# bytexplore_devboard.net
KiCad netlist of a schematic drawn in EAGLE
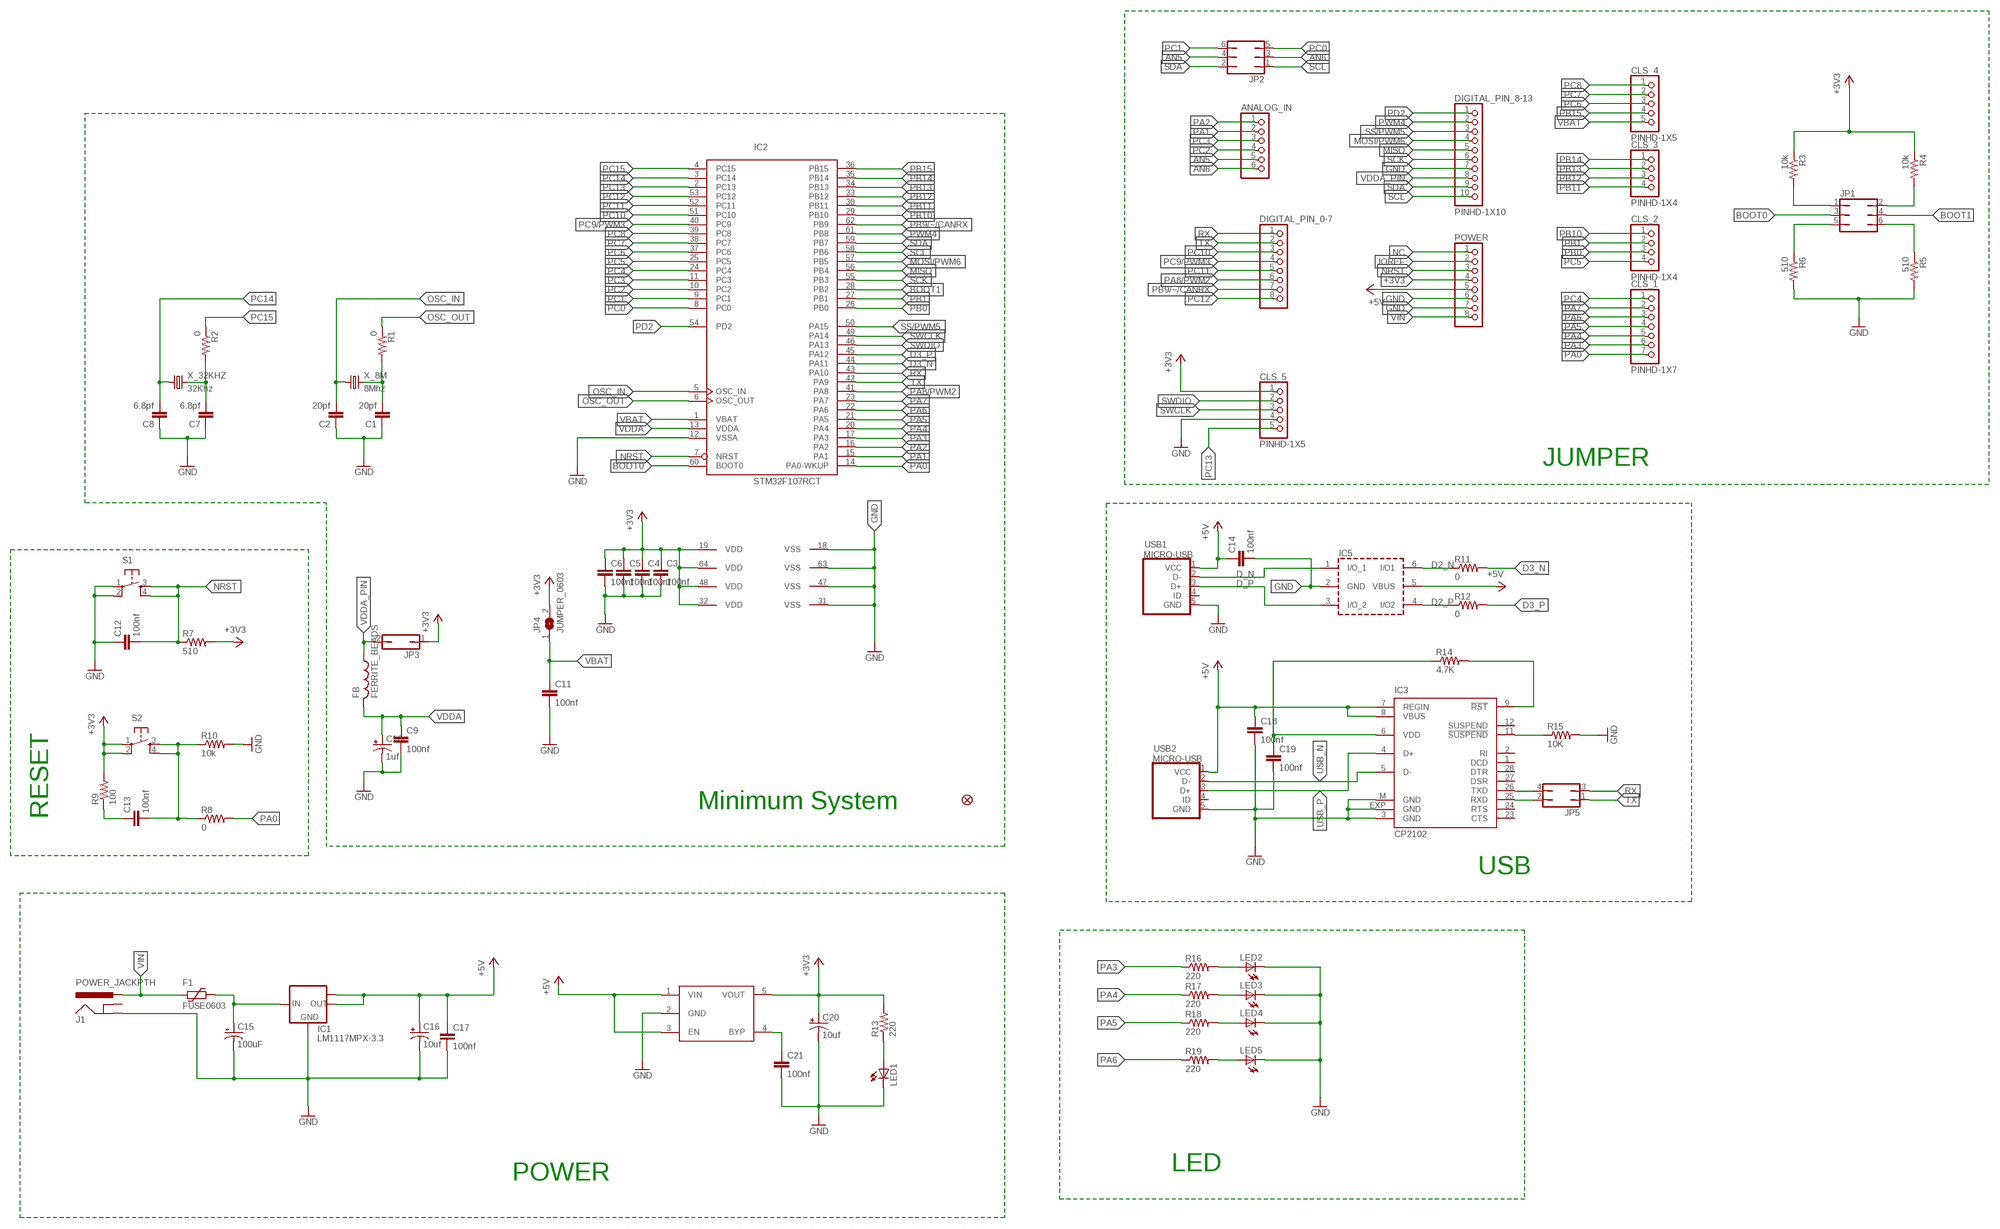
[diagram p0: schematic, sheet 1]

(export (version "E")
  (design (tool "Eeschema 10.0.6"))
  (components
    (comp (ref "ANALOG_IN")
      (value "PINHD-1X6B")
      (footprint "eagle-import:1X06-BIG")
      (libsource (lib "eagle-import") (part "PINHD-1X6B"))
    )
    (comp (ref "C1")
      (value "20pf")
      (footprint "eagle-import:C0603K")
      (libsource (lib "eagle-import") (part "C-EUC0603K"))
    )
    (comp (ref "C2")
      (value "20pf")
      (footprint "eagle-import:C0603K")
      (libsource (lib "eagle-import") (part "C-EUC0603K"))
    )
    (comp (ref "C3")
      (value "100nf")
      (footprint "eagle-import:C0603K")
      (libsource (lib "eagle-import") (part "C-EUC0603K"))
    )
    (comp (ref "C4")
      (value "100nf")
      (footprint "eagle-import:C0603K")
      (libsource (lib "eagle-import") (part "C-EUC0603K"))
    )
    (comp (ref "C5")
      (value "100nf")
      (footprint "eagle-import:C0603K")
      (libsource (lib "eagle-import") (part "C-EUC0603K"))
    )
    (comp (ref "C6")
      (value "100nf")
      (footprint "eagle-import:C0603K")
      (libsource (lib "eagle-import") (part "C-EUC0603K"))
    )
    (comp (ref "C7")
      (value "6.8pf")
      (footprint "eagle-import:C0603K")
      (libsource (lib "eagle-import") (part "C-EUC0603K"))
    )
    (comp (ref "C8")
      (value "6.8pf")
      (footprint "eagle-import:C0603K")
      (libsource (lib "eagle-import") (part "C-EUC0603K"))
    )
    (comp (ref "C9")
      (value "100nf")
      (footprint "eagle-import:C0603K")
      (libsource (lib "eagle-import") (part "C-EUC0603K"))
    )
    (comp (ref "C10")
      (value "1uf")
      (footprint "eagle-import:SMC_B")
      (libsource (lib "eagle-import") (part "CPOL-USSMCB"))
    )
    (comp (ref "C11")
      (value "100nf")
      (footprint "eagle-import:C0603K")
      (libsource (lib "eagle-import") (part "C-EUC0603K"))
    )
    (comp (ref "C12")
      (value "100nf")
      (footprint "eagle-import:C0603K")
      (libsource (lib "eagle-import") (part "C-EUC0603K"))
    )
    (comp (ref "C13")
      (value "100nf")
      (footprint "eagle-import:C0603K")
      (libsource (lib "eagle-import") (part "C-EUC0603K"))
    )
    (comp (ref "C14")
      (value "100nf")
      (footprint "eagle-import:C0603K")
      (libsource (lib "eagle-import") (part "C-EUC0603K"))
    )
    (comp (ref "C15")
      (value "100uF")
      (footprint "eagle-import:PANASONIC_D")
      (libsource (lib "eagle-import") (part "CPOL-USD"))
    )
    (comp (ref "C16")
      (value "10uf")
      (footprint "eagle-import:PANASONIC_B")
      (libsource (lib "eagle-import") (part "CPOL-USB"))
    )
    (comp (ref "C17")
      (value "100nf")
      (footprint "eagle-import:C0603")
      (libsource (lib "eagle-import") (part "C-EUC0603"))
    )
    (comp (ref "C18")
      (value "100nf")
      (footprint "eagle-import:C0603K")
      (libsource (lib "eagle-import") (part "C-EUC0603K"))
    )
    (comp (ref "C19")
      (value "100nf")
      (footprint "eagle-import:C0603K")
      (libsource (lib "eagle-import") (part "C-EUC0603K"))
    )
    (comp (ref "C20")
      (value "10uf")
      (footprint "eagle-import:SMC_A")
      (libsource (lib "eagle-import") (part "CPOL-USSMCA"))
    )
    (comp (ref "C21")
      (value "100nf")
      (footprint "eagle-import:C0603")
      (libsource (lib "eagle-import") (part "C-EUC0603"))
    )
    (comp (ref "CLS_1")
      (value "PINHD-1X7")
      (footprint "eagle-import:1X07-BIG")
      (libsource (lib "eagle-import") (part "PINHD-1X7"))
    )
    (comp (ref "CLS_2")
      (value "PINHD-1X4")
      (footprint "eagle-import:1X04-BIG")
      (libsource (lib "eagle-import") (part "PINHD-1X4"))
    )
    (comp (ref "CLS_3")
      (value "PINHD-1X4")
      (footprint "eagle-import:1X04-BIG")
      (libsource (lib "eagle-import") (part "PINHD-1X4"))
    )
    (comp (ref "CLS_4")
      (value "PINHD-1X5")
      (footprint "eagle-import:1X05-BIG")
      (libsource (lib "eagle-import") (part "PINHD-1X5"))
    )
    (comp (ref "CLS_5")
      (value "PINHD-1X5")
      (footprint "eagle-import:1X05-BIG")
      (libsource (lib "eagle-import") (part "PINHD-1X5"))
    )
    (comp (ref "DIGITAL_PIN_0-7")
      (value "PINHD-1X8BIG")
      (footprint "eagle-import:1X08-BIG")
      (libsource (lib "eagle-import") (part "PINHD-1X8BIG"))
    )
    (comp (ref "DIGITAL_PIN_8-13")
      (value "PINHD-1X10")
      (footprint "eagle-import:1X10-BIG")
      (libsource (lib "eagle-import") (part "PINHD-1X10"))
    )
    (comp (ref "F1")
      (value "FUSE0603")
      (footprint "eagle-import:R0603")
      (libsource (lib "eagle-import") (part "FUSE0603"))
    )
    (comp (ref "FB")
      (value "FERRITE_BEADS")
      (footprint "eagle-import:R0603")
      (libsource (lib "eagle-import") (part "FERRITE_BEADS"))
    )
    (comp (ref "IC1")
      (value "LM1117MPX-3.3")
      (footprint "eagle-import:SOT223")
      (libsource (lib "eagle-import") (part "LM1117MPX-3.3"))
    )
    (comp (ref "IC2")
      (value "STM32F107RCT")
      (footprint "eagle-import:LQFP64")
      (libsource (lib "eagle-import") (part "STM32F107RTC"))
    )
    (comp (ref "IC3")
      (value "CP2102")
      (footprint "eagle-import:MLP28")
      (fields (field (name "MF") "FARNELL") (field (name "MPN") "CP2102-GM"))
      (libsource (lib "eagle-import") (part "CP2102"))
    )
    (comp (ref "IC4")
      (value "MIC5219")
      (footprint "eagle-import:SOT-23-5")
      (libsource (lib "eagle-import") (part "MIC5219"))
    )
    (comp (ref "IC5")
      (value "USBLC6-2SC6")
      (footprint "eagle-import:SOT-23-6L")
      (libsource (lib "eagle-import") (part "USBLC6-2SC6"))
    )
    (comp (ref "J1")
      (value "POWER_JACKPTH")
      (footprint "eagle-import:POWER_JACK_PTH")
      (libsource (lib "eagle-import") (part "POWER_JACKPTH"))
    )
    (comp (ref "JP1")
      (value "JP3Q")
      (footprint "eagle-import:JP3Q")
      (libsource (lib "eagle-import") (part "JP3Q"))
    )
    (comp (ref "JP2")
      (value "JP3Q")
      (footprint "eagle-import:JP3Q")
      (libsource (lib "eagle-import") (part "JP3Q"))
    )
    (comp (ref "JP3")
      (value "JP1Q")
      (footprint "eagle-import:JP1")
      (libsource (lib "eagle-import") (part "JP1Q"))
    )
    (comp (ref "JP4")
      (value "JUMPER_0603")
      (footprint "eagle-import:R0603")
      (libsource (lib "eagle-import") (part "JUMPER_0603"))
    )
    (comp (ref "JP5")
      (value "JP2Q")
      (footprint "eagle-import:JP2Q")
      (libsource (lib "eagle-import") (part "JP2Q"))
    )
    (comp (ref "JP6")
      (value "FIDUCIAL1X2")
      (footprint "eagle-import:FIDUCIAL-1X2")
      (libsource (lib "eagle-import") (part "FIDUCIAL1X2"))
    )
    (comp (ref "LED1")
      (value "LEDSML0603")
      (footprint "eagle-import:SML0603")
      (libsource (lib "eagle-import") (part "LEDSML0603"))
    )
    (comp (ref "LED2")
      (value "LEDSML0603")
      (footprint "eagle-import:SML0603")
      (libsource (lib "eagle-import") (part "LEDSML0603"))
    )
    (comp (ref "LED3")
      (value "LEDSML0603")
      (footprint "eagle-import:SML0603")
      (libsource (lib "eagle-import") (part "LEDSML0603"))
    )
    (comp (ref "LED4")
      (value "LEDSML0603")
      (footprint "eagle-import:SML0603")
      (libsource (lib "eagle-import") (part "LEDSML0603"))
    )
    (comp (ref "LED5")
      (value "LEDSML0603")
      (footprint "eagle-import:SML0603")
      (libsource (lib "eagle-import") (part "LEDSML0603"))
    )
    (comp (ref "POWER")
      (value "PINHD-1X8BIG")
      (footprint "eagle-import:1X08-BIG")
      (libsource (lib "eagle-import") (part "PINHD-1X8BIG"))
    )
    (comp (ref "R1")
      (value "0")
      (footprint "eagle-import:R0603")
      (libsource (lib "eagle-import") (part "R-US_R0603"))
    )
    (comp (ref "R2")
      (value "0")
      (footprint "eagle-import:R0603")
      (libsource (lib "eagle-import") (part "R-US_R0603"))
    )
    (comp (ref "R3")
      (value "10k")
      (footprint "eagle-import:R0603")
      (libsource (lib "eagle-import") (part "R-US_R0603"))
    )
    (comp (ref "R4")
      (value "10k")
      (footprint "eagle-import:R0603")
      (libsource (lib "eagle-import") (part "R-US_R0603"))
    )
    (comp (ref "R5")
      (value "510")
      (footprint "eagle-import:R0603")
      (libsource (lib "eagle-import") (part "R-US_R0603"))
    )
    (comp (ref "R6")
      (value "510")
      (footprint "eagle-import:R0603")
      (libsource (lib "eagle-import") (part "R-US_R0603"))
    )
    (comp (ref "R7")
      (value "510")
      (footprint "eagle-import:R0603")
      (libsource (lib "eagle-import") (part "R-US_R0603"))
    )
    (comp (ref "R8")
      (value "0")
      (footprint "eagle-import:R0603")
      (libsource (lib "eagle-import") (part "R-US_R0603"))
    )
    (comp (ref "R9")
      (value "100")
      (footprint "eagle-import:R0603")
      (libsource (lib "eagle-import") (part "R-US_R0603"))
    )
    (comp (ref "R10")
      (value "10k")
      (footprint "eagle-import:R0603")
      (libsource (lib "eagle-import") (part "R-US_R0603"))
    )
    (comp (ref "R11")
      (value "0")
      (footprint "eagle-import:R0603")
      (libsource (lib "eagle-import") (part "R-US_R0603"))
    )
    (comp (ref "R12")
      (value "0")
      (footprint "eagle-import:R0603")
      (libsource (lib "eagle-import") (part "R-US_R0603"))
    )
    (comp (ref "R13")
      (value "220")
      (footprint "eagle-import:R0603")
      (libsource (lib "eagle-import") (part "R-US_R0603"))
    )
    (comp (ref "R14")
      (value "4.7K")
      (footprint "eagle-import:R0603")
      (libsource (lib "eagle-import") (part "R-US_R0603"))
    )
    (comp (ref "R15")
      (value "10K")
      (footprint "eagle-import:R0603")
      (libsource (lib "eagle-import") (part "R-US_R0603"))
    )
    (comp (ref "R16")
      (value "220")
      (footprint "eagle-import:R0603")
      (libsource (lib "eagle-import") (part "R-US_R0603"))
    )
    (comp (ref "R17")
      (value "220")
      (footprint "eagle-import:R0603")
      (libsource (lib "eagle-import") (part "R-US_R0603"))
    )
    (comp (ref "R18")
      (value "220")
      (footprint "eagle-import:R0603")
      (libsource (lib "eagle-import") (part "R-US_R0603"))
    )
    (comp (ref "R19")
      (value "220")
      (footprint "eagle-import:R0603")
      (libsource (lib "eagle-import") (part "R-US_R0603"))
    )
    (comp (ref "S1")
      (value "TAC_SWITCHPTH")
      (footprint "eagle-import:TACTILE-PTH")
      (libsource (lib "eagle-import") (part "TAC_SWITCHPTH"))
    )
    (comp (ref "S2")
      (value "TAC_SWITCHPTH")
      (footprint "eagle-import:TACTILE-PTH")
      (libsource (lib "eagle-import") (part "TAC_SWITCHPTH"))
    )
    (comp (ref "USB1")
      (value "MICRO-USB")
      (footprint "eagle-import:MICRO-USB")
      (libsource (lib "eagle-import") (part "MICRO-USB"))
    )
    (comp (ref "USB2")
      (value "MICRO-USB")
      (footprint "eagle-import:MICRO-USB")
      (libsource (lib "eagle-import") (part "MICRO-USB"))
    )
    (comp (ref "X_8M")
      (value "8Mhz")
      (footprint "eagle-import:HC49U70")
      (libsource (lib "eagle-import") (part "CRYSTALHC49U70"))
    )
    (comp (ref "X_32KHZ")
      (value "32Khz")
      (footprint "eagle-import:TC26H")
      (libsource (lib "eagle-import") (part "CRYSTALTC26H"))
    )
  )
  (nets
    (net (code "1") (name "+3V3") (class "Default")
      (node (ref "C20") (pin "+") (pinfunction "+_+") (pintype "passive"))
      (node (ref "C3") (pin "1") (pinfunction "1_1") (pintype "passive"))
      (node (ref "C4") (pin "1") (pinfunction "1_1") (pintype "passive"))
      (node (ref "C5") (pin "1") (pinfunction "1_1") (pintype "passive"))
      (node (ref "C6") (pin "1") (pinfunction "1_1") (pintype "passive"))
      (node (ref "CLS_5") (pin "1") (pinfunction "1_1") (pintype "passive"))
      (node (ref "IC2") (pin "19") (pinfunction "VDD_19") (pintype "power_in"))
      (node (ref "IC2") (pin "32") (pinfunction "VDD_32") (pintype "power_in"))
      (node (ref "IC2") (pin "48") (pinfunction "VDD_48") (pintype "power_in"))
      (node (ref "IC2") (pin "64") (pinfunction "VDD_64") (pintype "power_in"))
      (node (ref "IC4") (pin "5") (pinfunction "VOUT_5") (pintype "bidirectional"))
      (node (ref "JP3") (pin "1") (pinfunction "1_1") (pintype "passive"))
      (node (ref "JP4") (pin "2") (pinfunction "2_2") (pintype "passive"))
      (node (ref "POWER") (pin "4") (pinfunction "4_4") (pintype "passive"))
      (node (ref "R13") (pin "2") (pinfunction "2_2") (pintype "passive"))
      (node (ref "R3") (pin "1") (pinfunction "1_1") (pintype "passive"))
      (node (ref "R4") (pin "1") (pinfunction "1_1") (pintype "passive"))
      (node (ref "R7") (pin "2") (pinfunction "2_2") (pintype "passive"))
      (node (ref "R9") (pin "2") (pinfunction "2_2") (pintype "passive"))
      (node (ref "S2") (pin "1") (pinfunction "1_1") (pintype "passive"))
      (node (ref "S2") (pin "2") (pinfunction "2_2") (pintype "passive"))
    )
    (net (code "2") (name "+5V") (class "Default")
      (node (ref "C14") (pin "1") (pinfunction "1_1") (pintype "passive"))
      (node (ref "C16") (pin "+") (pinfunction "+_+") (pintype "passive"))
      (node (ref "C17") (pin "1") (pinfunction "1_1") (pintype "passive"))
      (node (ref "C18") (pin "1") (pinfunction "1_1") (pintype "passive"))
      (node (ref "IC1") (pin "2") (pinfunction "OUT_2") (pintype "passive"))
      (node (ref "IC1") (pin "TAB") (pinfunction "OUT1_TAB") (pintype "passive"))
      (node (ref "IC3") (pin "7") (pinfunction "REGIN_7") (pintype "passive"))
      (node (ref "IC3") (pin "8") (pinfunction "VBUS_8") (pintype "input"))
      (node (ref "IC4") (pin "1") (pinfunction "VIN_1") (pintype "bidirectional"))
      (node (ref "IC4") (pin "3") (pinfunction "EN_3") (pintype "bidirectional"))
      (node (ref "IC5") (pin "5") (pinfunction "VBUS_5") (pintype "bidirectional"))
      (node (ref "POWER") (pin "5") (pinfunction "5_5") (pintype "passive"))
      (node (ref "USB1") (pin "1") (pinfunction "VCC_1") (pintype "power_in"))
      (node (ref "USB2") (pin "1") (pinfunction "VCC_1") (pintype "power_in"))
    )
    (net (code "3") (name "/D2_N") (class "Default")
      (node (ref "IC5") (pin "6") (pinfunction "I/O1_6") (pintype "bidirectional"))
      (node (ref "R11") (pin "1") (pinfunction "1_1") (pintype "passive"))
    )
    (net (code "4") (name "/D2_P") (class "Default")
      (node (ref "IC5") (pin "4") (pinfunction "I/O2_4") (pintype "bidirectional"))
      (node (ref "R12") (pin "1") (pinfunction "1_1") (pintype "passive"))
    )
    (net (code "5") (name "/D_N") (class "Default")
      (node (ref "IC5") (pin "1") (pinfunction "I/O_1_1") (pintype "bidirectional"))
      (node (ref "USB1") (pin "2") (pinfunction "D-_2") (pintype "bidirectional"))
    )
    (net (code "6") (name "/D_P") (class "Default")
      (node (ref "IC5") (pin "3") (pinfunction "I/O_2_3") (pintype "bidirectional"))
      (node (ref "USB1") (pin "3") (pinfunction "D+_3") (pintype "bidirectional"))
    )
    (net (code "7") (name "/PB9{slash}~{{slash}CANRX}") (class "Default")
      (node (ref "DIGITAL_PIN_0-7") (pin "7") (pinfunction "7_7") (pintype "passive"))
      (node (ref "IC2") (pin "62") (pinfunction "PB9_62") (pintype "bidirectional"))
    )
    (net (code "8") (name "AN5") (class "Default")
      (node (ref "ANALOG_IN") (pin "5") (pinfunction "5_5") (pintype "passive"))
      (node (ref "JP2") (pin "4") (pinfunction "4_4") (pintype "passive"))
    )
    (net (code "9") (name "AN6") (class "Default")
      (node (ref "ANALOG_IN") (pin "6") (pinfunction "6_6") (pintype "passive"))
      (node (ref "JP2") (pin "3") (pinfunction "3_3") (pintype "passive"))
    )
    (net (code "10") (name "BOOT0") (class "Default")
      (node (ref "IC2") (pin "60") (pinfunction "BOOT0_60") (pintype "input"))
      (node (ref "JP1") (pin "3") (pinfunction "3_3") (pintype "passive"))
    )
    (net (code "11") (name "BOOT1") (class "Default")
      (node (ref "IC2") (pin "28") (pinfunction "PB2_28") (pintype "bidirectional"))
      (node (ref "JP1") (pin "4") (pinfunction "4_4") (pintype "passive"))
    )
    (net (code "12") (name "D3_N") (class "Default")
      (node (ref "IC2") (pin "44") (pinfunction "PA11_44") (pintype "bidirectional"))
      (node (ref "R11") (pin "2") (pinfunction "2_2") (pintype "passive"))
    )
    (net (code "13") (name "D3_P") (class "Default")
      (node (ref "IC2") (pin "45") (pinfunction "PA12_45") (pintype "bidirectional"))
      (node (ref "R12") (pin "2") (pinfunction "2_2") (pintype "passive"))
    )
    (net (code "14") (name "GND") (class "Default")
      (node (ref "C1") (pin "1") (pinfunction "1_1") (pintype "passive"))
      (node (ref "C10") (pin "-") (pinfunction "-_-") (pintype "passive"))
      (node (ref "C11") (pin "2") (pinfunction "2_2") (pintype "passive"))
      (node (ref "C12") (pin "1") (pinfunction "1_1") (pintype "passive"))
      (node (ref "C14") (pin "2") (pinfunction "2_2") (pintype "passive"))
      (node (ref "C15") (pin "-") (pinfunction "-_-") (pintype "passive"))
      (node (ref "C16") (pin "-") (pinfunction "-_-") (pintype "passive"))
      (node (ref "C17") (pin "2") (pinfunction "2_2") (pintype "passive"))
      (node (ref "C18") (pin "2") (pinfunction "2_2") (pintype "passive"))
      (node (ref "C19") (pin "2") (pinfunction "2_2") (pintype "passive"))
      (node (ref "C2") (pin "1") (pinfunction "1_1") (pintype "passive"))
      (node (ref "C20") (pin "-") (pinfunction "-_-") (pintype "passive"))
      (node (ref "C21") (pin "2") (pinfunction "2_2") (pintype "passive"))
      (node (ref "C3") (pin "2") (pinfunction "2_2") (pintype "passive"))
      (node (ref "C4") (pin "2") (pinfunction "2_2") (pintype "passive"))
      (node (ref "C5") (pin "2") (pinfunction "2_2") (pintype "passive"))
      (node (ref "C6") (pin "2") (pinfunction "2_2") (pintype "passive"))
      (node (ref "C7") (pin "1") (pinfunction "1_1") (pintype "passive"))
      (node (ref "C8") (pin "1") (pinfunction "1_1") (pintype "passive"))
      (node (ref "C9") (pin "2") (pinfunction "2_2") (pintype "passive"))
      (node (ref "CLS_5") (pin "4") (pinfunction "4_4") (pintype "passive"))
      (node (ref "DIGITAL_PIN_8-13") (pin "7") (pinfunction "7_7") (pintype "passive"))
      (node (ref "IC1") (pin "1") (pinfunction "GND_1") (pintype "input"))
      (node (ref "IC2") (pin "12") (pinfunction "VSSA_12") (pintype "power_in"))
      (node (ref "IC2") (pin "18") (pinfunction "VSS_18") (pintype "power_in"))
      (node (ref "IC2") (pin "31") (pinfunction "VSS_31") (pintype "power_in"))
      (node (ref "IC2") (pin "47") (pinfunction "VSS_47") (pintype "power_in"))
      (node (ref "IC2") (pin "63") (pinfunction "VSS_63") (pintype "power_in"))
      (node (ref "IC3") (pin "3") (pinfunction "GND_3") (pintype "power_in"))
      (node (ref "IC3") (pin "EXP") (pinfunction "GND_EXP") (pintype "power_in"))
      (node (ref "IC3") (pin "M") (pinfunction "GND_M") (pintype "power_in"))
      (node (ref "IC4") (pin "2") (pinfunction "GND_2") (pintype "bidirectional"))
      (node (ref "IC5") (pin "2") (pinfunction "GND_2") (pintype "bidirectional"))
      (node (ref "J1") (pin "GND") (pinfunction "GND_GND") (pintype "bidirectional"))
      (node (ref "LED1") (pin "C") (pinfunction "C_C") (pintype "passive"))
      (node (ref "LED2") (pin "C") (pinfunction "C_C") (pintype "passive"))
      (node (ref "LED3") (pin "C") (pinfunction "C_C") (pintype "passive"))
      (node (ref "LED4") (pin "C") (pinfunction "C_C") (pintype "passive"))
      (node (ref "LED5") (pin "C") (pinfunction "C_C") (pintype "passive"))
      (node (ref "POWER") (pin "6") (pinfunction "6_6") (pintype "passive"))
      (node (ref "POWER") (pin "7") (pinfunction "7_7") (pintype "passive"))
      (node (ref "R10") (pin "2") (pinfunction "2_2") (pintype "passive"))
      (node (ref "R15") (pin "2") (pinfunction "2_2") (pintype "passive"))
      (node (ref "R5") (pin "2") (pinfunction "2_2") (pintype "passive"))
      (node (ref "R6") (pin "2") (pinfunction "2_2") (pintype "passive"))
      (node (ref "S1") (pin "1") (pinfunction "1_1") (pintype "passive"))
      (node (ref "S1") (pin "2") (pinfunction "2_2") (pintype "passive"))
      (node (ref "USB1") (pin "5") (pinfunction "GND_5") (pintype "power_in"))
      (node (ref "USB2") (pin "5") (pinfunction "GND_5") (pintype "power_in"))
    )
    (net (code "15") (name "IOREF") (class "Default")
      (node (ref "POWER") (pin "2") (pinfunction "2_2") (pintype "passive"))
    )
    (net (code "16") (name "MISO") (class "Default")
      (node (ref "DIGITAL_PIN_8-13") (pin "5") (pinfunction "5_5") (pintype "passive"))
      (node (ref "IC2") (pin "56") (pinfunction "PB4_56") (pintype "bidirectional"))
    )
    (net (code "17") (name "MOSI{slash}PWM6") (class "Default")
      (node (ref "DIGITAL_PIN_8-13") (pin "4") (pinfunction "4_4") (pintype "passive"))
      (node (ref "IC2") (pin "57") (pinfunction "PB5_57") (pintype "bidirectional"))
    )
    (net (code "18") (name "NC") (class "Default")
      (node (ref "POWER") (pin "1") (pinfunction "1_1") (pintype "passive"))
    )
    (net (code "19") (name "NRST") (class "Default")
      (node (ref "C12") (pin "2") (pinfunction "2_2") (pintype "passive"))
      (node (ref "IC2") (pin "7") (pinfunction "NRST_7") (pintype "bidirectional"))
      (node (ref "POWER") (pin "3") (pinfunction "3_3") (pintype "passive"))
      (node (ref "R7") (pin "1") (pinfunction "1_1") (pintype "passive"))
      (node (ref "S1") (pin "3") (pinfunction "3_3") (pintype "passive"))
      (node (ref "S1") (pin "4") (pinfunction "4_4") (pintype "passive"))
    )
    (net (code "20") (name "Net-(C1-Pad2)") (class "Default")
      (node (ref "C1") (pin "2") (pinfunction "2_2") (pintype "passive"))
      (node (ref "R1") (pin "2") (pinfunction "2_2") (pintype "passive"))
      (node (ref "X_8M") (pin "2") (pinfunction "2_2") (pintype "passive"))
    )
    (net (code "21") (name "Net-(C7-Pad2)") (class "Default")
      (node (ref "C7") (pin "2") (pinfunction "2_2") (pintype "passive"))
      (node (ref "R2") (pin "2") (pinfunction "2_2") (pintype "passive"))
      (node (ref "X_32KHZ") (pin "2") (pinfunction "2_2") (pintype "passive"))
    )
    (net (code "22") (name "Net-(C13-Pad1)") (class "Default")
      (node (ref "C13") (pin "1") (pinfunction "1_1") (pintype "passive"))
      (node (ref "R9") (pin "1") (pinfunction "1_1") (pintype "passive"))
    )
    (net (code "23") (name "Net-(C13-Pad2)") (class "Default")
      (node (ref "C13") (pin "2") (pinfunction "2_2") (pintype "passive"))
      (node (ref "R10") (pin "1") (pinfunction "1_1") (pintype "passive"))
      (node (ref "R8") (pin "1") (pinfunction "1_1") (pintype "passive"))
      (node (ref "S2") (pin "3") (pinfunction "3_3") (pintype "passive"))
      (node (ref "S2") (pin "4") (pinfunction "4_4") (pintype "passive"))
    )
    (net (code "24") (name "Net-(IC1-IN)") (class "Default")
      (node (ref "C15") (pin "+") (pinfunction "+_+") (pintype "passive"))
      (node (ref "F1") (pin "1") (pinfunction "1_1") (pintype "passive"))
      (node (ref "IC1") (pin "3") (pinfunction "IN_3") (pintype "input"))
    )
    (net (code "25") (name "Net-(IC3-RXD)") (class "Default")
      (node (ref "IC3") (pin "25") (pinfunction "RXD_25") (pintype "input"))
      (node (ref "JP5") (pin "2") (pinfunction "2_2") (pintype "passive"))
    )
    (net (code "26") (name "Net-(IC3-TXD)") (class "Default")
      (node (ref "IC3") (pin "26") (pinfunction "TXD_26") (pintype "output"))
      (node (ref "JP5") (pin "4") (pinfunction "4_4") (pintype "passive"))
    )
    (net (code "27") (name "Net-(IC3-VDD)") (class "Default")
      (node (ref "C19") (pin "1") (pinfunction "1_1") (pintype "passive"))
      (node (ref "IC3") (pin "6") (pinfunction "VDD_6") (pintype "power_in"))
      (node (ref "R14") (pin "1") (pinfunction "1_1") (pintype "passive"))
    )
    (net (code "28") (name "Net-(IC3-~{RST})") (class "Default")
      (node (ref "IC3") (pin "9") (pinfunction "~{RST}_9") (pintype "bidirectional"))
      (node (ref "R14") (pin "2") (pinfunction "2_2") (pintype "passive"))
    )
    (net (code "29") (name "Net-(IC3-~{SUSPEND})") (class "Default")
      (node (ref "IC3") (pin "11") (pinfunction "~{SUSPEND}_11") (pintype "output"))
      (node (ref "R15") (pin "1") (pinfunction "1_1") (pintype "passive"))
    )
    (net (code "30") (name "Net-(IC4-BYP)") (class "Default")
      (node (ref "C21") (pin "1") (pinfunction "1_1") (pintype "passive"))
      (node (ref "IC4") (pin "4") (pinfunction "BYP_4") (pintype "bidirectional"))
    )
    (net (code "31") (name "Net-(JP1-Pad1)") (class "Default")
      (node (ref "JP1") (pin "1") (pinfunction "1_1") (pintype "passive"))
      (node (ref "R3") (pin "2") (pinfunction "2_2") (pintype "passive"))
    )
    (net (code "32") (name "Net-(JP1-Pad2)") (class "Default")
      (node (ref "JP1") (pin "2") (pinfunction "2_2") (pintype "passive"))
      (node (ref "R4") (pin "2") (pinfunction "2_2") (pintype "passive"))
    )
    (net (code "33") (name "Net-(JP1-Pad5)") (class "Default")
      (node (ref "JP1") (pin "5") (pinfunction "5_5") (pintype "passive"))
      (node (ref "R6") (pin "1") (pinfunction "1_1") (pintype "passive"))
    )
    (net (code "34") (name "Net-(JP1-Pad6)") (class "Default")
      (node (ref "JP1") (pin "6") (pinfunction "6_6") (pintype "passive"))
      (node (ref "R5") (pin "1") (pinfunction "1_1") (pintype "passive"))
    )
    (net (code "35") (name "Net-(LED1-PadA)") (class "Default")
      (node (ref "LED1") (pin "A") (pinfunction "A_A") (pintype "passive"))
      (node (ref "R13") (pin "1") (pinfunction "1_1") (pintype "passive"))
    )
    (net (code "36") (name "Net-(LED2-PadA)") (class "Default")
      (node (ref "LED2") (pin "A") (pinfunction "A_A") (pintype "passive"))
      (node (ref "R16") (pin "2") (pinfunction "2_2") (pintype "passive"))
    )
    (net (code "37") (name "Net-(LED3-PadA)") (class "Default")
      (node (ref "LED3") (pin "A") (pinfunction "A_A") (pintype "passive"))
      (node (ref "R17") (pin "2") (pinfunction "2_2") (pintype "passive"))
    )
    (net (code "38") (name "Net-(LED4-PadA)") (class "Default")
      (node (ref "LED4") (pin "A") (pinfunction "A_A") (pintype "passive"))
      (node (ref "R18") (pin "2") (pinfunction "2_2") (pintype "passive"))
    )
    (net (code "39") (name "Net-(LED5-PadA)") (class "Default")
      (node (ref "LED5") (pin "A") (pinfunction "A_A") (pintype "passive"))
      (node (ref "R19") (pin "2") (pinfunction "2_2") (pintype "passive"))
    )
    (net (code "40") (name "OSC_IN") (class "Default")
      (node (ref "C2") (pin "2") (pinfunction "2_2") (pintype "passive"))
      (node (ref "IC2") (pin "5") (pinfunction "OSC_IN_5") (pintype "bidirectional"))
      (node (ref "X_8M") (pin "1") (pinfunction "1_1") (pintype "passive"))
    )
    (net (code "41") (name "OSC_OUT") (class "Default")
      (node (ref "IC2") (pin "6") (pinfunction "OSC_OUT_6") (pintype "bidirectional"))
      (node (ref "R1") (pin "1") (pinfunction "1_1") (pintype "passive"))
    )
    (net (code "42") (name "PA0") (class "Default")
      (node (ref "CLS_1") (pin "7") (pinfunction "7_7") (pintype "passive"))
      (node (ref "IC2") (pin "14") (pinfunction "PA0-WKUP_14") (pintype "bidirectional"))
      (node (ref "R8") (pin "2") (pinfunction "2_2") (pintype "passive"))
    )
    (net (code "43") (name "PA1") (class "Default")
      (node (ref "ANALOG_IN") (pin "2") (pinfunction "2_2") (pintype "passive"))
      (node (ref "IC2") (pin "15") (pinfunction "PA1_15") (pintype "bidirectional"))
    )
    (net (code "44") (name "PA2") (class "Default")
      (node (ref "ANALOG_IN") (pin "1") (pinfunction "1_1") (pintype "passive"))
      (node (ref "IC2") (pin "16") (pinfunction "PA2_16") (pintype "bidirectional"))
    )
    (net (code "45") (name "PA3") (class "Default")
      (node (ref "CLS_1") (pin "6") (pinfunction "6_6") (pintype "passive"))
      (node (ref "IC2") (pin "17") (pinfunction "PA3_17") (pintype "bidirectional"))
      (node (ref "R16") (pin "1") (pinfunction "1_1") (pintype "passive"))
    )
    (net (code "46") (name "PA4") (class "Default")
      (node (ref "CLS_1") (pin "5") (pinfunction "5_5") (pintype "passive"))
      (node (ref "IC2") (pin "20") (pinfunction "PA4_20") (pintype "bidirectional"))
      (node (ref "R17") (pin "1") (pinfunction "1_1") (pintype "passive"))
    )
    (net (code "47") (name "PA5") (class "Default")
      (node (ref "CLS_1") (pin "4") (pinfunction "4_4") (pintype "passive"))
      (node (ref "IC2") (pin "21") (pinfunction "PA5_21") (pintype "bidirectional"))
      (node (ref "R18") (pin "1") (pinfunction "1_1") (pintype "passive"))
    )
    (net (code "48") (name "PA6") (class "Default")
      (node (ref "CLS_1") (pin "3") (pinfunction "3_3") (pintype "passive"))
      (node (ref "IC2") (pin "22") (pinfunction "PA6_22") (pintype "bidirectional"))
      (node (ref "R19") (pin "1") (pinfunction "1_1") (pintype "passive"))
    )
    (net (code "49") (name "PA7") (class "Default")
      (node (ref "CLS_1") (pin "2") (pinfunction "2_2") (pintype "passive"))
      (node (ref "IC2") (pin "23") (pinfunction "PA7_23") (pintype "bidirectional"))
    )
    (net (code "50") (name "PA8{slash}PWM2") (class "Default")
      (node (ref "DIGITAL_PIN_0-7") (pin "6") (pinfunction "6_6") (pintype "passive"))
      (node (ref "IC2") (pin "41") (pinfunction "PA8_41") (pintype "bidirectional"))
    )
    (net (code "51") (name "PB0") (class "Default")
      (node (ref "CLS_2") (pin "3") (pinfunction "3_3") (pintype "passive"))
      (node (ref "IC2") (pin "26") (pinfunction "PB0_26") (pintype "bidirectional"))
    )
    (net (code "52") (name "PB1") (class "Default")
      (node (ref "CLS_2") (pin "2") (pinfunction "2_2") (pintype "passive"))
      (node (ref "IC2") (pin "27") (pinfunction "PB1_27") (pintype "bidirectional"))
    )
    (net (code "53") (name "PB10") (class "Default")
      (node (ref "CLS_2") (pin "1") (pinfunction "1_1") (pintype "passive"))
      (node (ref "IC2") (pin "29") (pinfunction "PB10_29") (pintype "bidirectional"))
    )
    (net (code "54") (name "PB11") (class "Default")
      (node (ref "CLS_3") (pin "4") (pinfunction "4_4") (pintype "passive"))
      (node (ref "IC2") (pin "30") (pinfunction "PB11_30") (pintype "bidirectional"))
    )
    (net (code "55") (name "PB12") (class "Default")
      (node (ref "CLS_3") (pin "3") (pinfunction "3_3") (pintype "passive"))
      (node (ref "IC2") (pin "33") (pinfunction "PB12_33") (pintype "bidirectional"))
    )
    (net (code "56") (name "PB13") (class "Default")
      (node (ref "CLS_3") (pin "2") (pinfunction "2_2") (pintype "passive"))
      (node (ref "IC2") (pin "34") (pinfunction "PB13_34") (pintype "bidirectional"))
    )
    (net (code "57") (name "PB14") (class "Default")
      (node (ref "CLS_3") (pin "1") (pinfunction "1_1") (pintype "passive"))
      (node (ref "IC2") (pin "35") (pinfunction "PB14_35") (pintype "bidirectional"))
    )
    (net (code "58") (name "PB15") (class "Default")
      (node (ref "CLS_4") (pin "4") (pinfunction "4_4") (pintype "passive"))
      (node (ref "IC2") (pin "36") (pinfunction "PB15_36") (pintype "bidirectional"))
    )
    (net (code "59") (name "PC0") (class "Default")
      (node (ref "IC2") (pin "8") (pinfunction "PC0_8") (pintype "bidirectional"))
      (node (ref "JP2") (pin "5") (pinfunction "5_5") (pintype "passive"))
    )
    (net (code "60") (name "PC1") (class "Default")
      (node (ref "IC2") (pin "9") (pinfunction "PC1_9") (pintype "bidirectional"))
      (node (ref "JP2") (pin "6") (pinfunction "6_6") (pintype "passive"))
    )
    (net (code "61") (name "PC2") (class "Default")
      (node (ref "ANALOG_IN") (pin "4") (pinfunction "4_4") (pintype "passive"))
      (node (ref "IC2") (pin "10") (pinfunction "PC2_10") (pintype "bidirectional"))
    )
    (net (code "62") (name "PC3") (class "Default")
      (node (ref "ANALOG_IN") (pin "3") (pinfunction "3_3") (pintype "passive"))
      (node (ref "IC2") (pin "11") (pinfunction "PC3_11") (pintype "bidirectional"))
    )
    (net (code "63") (name "PC4") (class "Default")
      (node (ref "CLS_1") (pin "1") (pinfunction "1_1") (pintype "passive"))
      (node (ref "IC2") (pin "24") (pinfunction "PC4_24") (pintype "bidirectional"))
    )
    (net (code "64") (name "PC5") (class "Default")
      (node (ref "CLS_2") (pin "4") (pinfunction "4_4") (pintype "passive"))
      (node (ref "IC2") (pin "25") (pinfunction "PC5_25") (pintype "bidirectional"))
    )
    (net (code "65") (name "PC6") (class "Default")
      (node (ref "CLS_4") (pin "3") (pinfunction "3_3") (pintype "passive"))
      (node (ref "IC2") (pin "37") (pinfunction "PC6_37") (pintype "bidirectional"))
    )
    (net (code "66") (name "PC7") (class "Default")
      (node (ref "CLS_4") (pin "2") (pinfunction "2_2") (pintype "passive"))
      (node (ref "IC2") (pin "38") (pinfunction "PC7_38") (pintype "bidirectional"))
    )
    (net (code "67") (name "PC8") (class "Default")
      (node (ref "CLS_4") (pin "1") (pinfunction "1_1") (pintype "passive"))
      (node (ref "IC2") (pin "39") (pinfunction "PC8_39") (pintype "bidirectional"))
    )
    (net (code "68") (name "PC9{slash}PWM3") (class "Default")
      (node (ref "DIGITAL_PIN_0-7") (pin "4") (pinfunction "4_4") (pintype "passive"))
      (node (ref "IC2") (pin "40") (pinfunction "PC9_40") (pintype "bidirectional"))
    )
    (net (code "69") (name "PC10") (class "Default")
      (node (ref "DIGITAL_PIN_0-7") (pin "3") (pinfunction "3_3") (pintype "passive"))
      (node (ref "IC2") (pin "51") (pinfunction "PC10_51") (pintype "bidirectional"))
    )
    (net (code "70") (name "PC11") (class "Default")
      (node (ref "DIGITAL_PIN_0-7") (pin "5") (pinfunction "5_5") (pintype "passive"))
      (node (ref "IC2") (pin "52") (pinfunction "PC11_52") (pintype "bidirectional"))
    )
    (net (code "71") (name "PC12") (class "Default")
      (node (ref "DIGITAL_PIN_0-7") (pin "8") (pinfunction "8_8") (pintype "passive"))
      (node (ref "IC2") (pin "53") (pinfunction "PC12_53") (pintype "bidirectional"))
    )
    (net (code "72") (name "PC13") (class "Default")
      (node (ref "CLS_5") (pin "5") (pinfunction "5_5") (pintype "passive"))
      (node (ref "IC2") (pin "2") (pinfunction "PC13_2") (pintype "bidirectional"))
    )
    (net (code "73") (name "PC14") (class "Default")
      (node (ref "C8") (pin "2") (pinfunction "2_2") (pintype "passive"))
      (node (ref "IC2") (pin "3") (pinfunction "PC14_3") (pintype "bidirectional"))
      (node (ref "X_32KHZ") (pin "1") (pinfunction "1_1") (pintype "passive"))
    )
    (net (code "74") (name "PC15") (class "Default")
      (node (ref "IC2") (pin "4") (pinfunction "PC15_4") (pintype "bidirectional"))
      (node (ref "R2") (pin "1") (pinfunction "1_1") (pintype "passive"))
    )
    (net (code "75") (name "PD2") (class "Default")
      (node (ref "DIGITAL_PIN_8-13") (pin "1") (pinfunction "1_1") (pintype "passive"))
      (node (ref "IC2") (pin "54") (pinfunction "PD2_54") (pintype "bidirectional"))
    )
    (net (code "76") (name "PWM4") (class "Default")
      (node (ref "DIGITAL_PIN_8-13") (pin "2") (pinfunction "2_2") (pintype "passive"))
      (node (ref "IC2") (pin "61") (pinfunction "PB8_61") (pintype "bidirectional"))
    )
    (net (code "77") (name "RX") (class "Default")
      (node (ref "DIGITAL_PIN_0-7") (pin "1") (pinfunction "1_1") (pintype "passive"))
      (node (ref "IC2") (pin "43") (pinfunction "PA10_43") (pintype "bidirectional"))
      (node (ref "JP5") (pin "3") (pinfunction "3_3") (pintype "passive"))
    )
    (net (code "78") (name "SCK") (class "Default")
      (node (ref "DIGITAL_PIN_8-13") (pin "6") (pinfunction "6_6") (pintype "passive"))
      (node (ref "IC2") (pin "55") (pinfunction "PB3_55") (pintype "bidirectional"))
    )
    (net (code "79") (name "SCL") (class "Default")
      (node (ref "DIGITAL_PIN_8-13") (pin "10") (pinfunction "10_10") (pintype "passive"))
      (node (ref "IC2") (pin "58") (pinfunction "PB6_58") (pintype "bidirectional"))
      (node (ref "JP2") (pin "1") (pinfunction "1_1") (pintype "passive"))
    )
    (net (code "80") (name "SDA") (class "Default")
      (node (ref "DIGITAL_PIN_8-13") (pin "9") (pinfunction "9_9") (pintype "passive"))
      (node (ref "IC2") (pin "59") (pinfunction "PB7_59") (pintype "bidirectional"))
      (node (ref "JP2") (pin "2") (pinfunction "2_2") (pintype "passive"))
    )
    (net (code "81") (name "SS{slash}PWM5") (class "Default")
      (node (ref "DIGITAL_PIN_8-13") (pin "3") (pinfunction "3_3") (pintype "passive"))
      (node (ref "IC2") (pin "50") (pinfunction "PA15_50") (pintype "bidirectional"))
    )
    (net (code "82") (name "SWCLK") (class "Default")
      (node (ref "CLS_5") (pin "3") (pinfunction "3_3") (pintype "passive"))
      (node (ref "IC2") (pin "49") (pinfunction "PA14_49") (pintype "bidirectional"))
    )
    (net (code "83") (name "SWDIO") (class "Default")
      (node (ref "CLS_5") (pin "2") (pinfunction "2_2") (pintype "passive"))
      (node (ref "IC2") (pin "46") (pinfunction "PA13_46") (pintype "bidirectional"))
    )
    (net (code "84") (name "TX") (class "Default")
      (node (ref "DIGITAL_PIN_0-7") (pin "2") (pinfunction "2_2") (pintype "passive"))
      (node (ref "IC2") (pin "42") (pinfunction "PA9_42") (pintype "bidirectional"))
      (node (ref "JP5") (pin "1") (pinfunction "1_1") (pintype "passive"))
    )
    (net (code "85") (name "USB_N") (class "Default")
      (node (ref "IC3") (pin "5") (pinfunction "D-_5") (pintype "bidirectional"))
      (node (ref "USB2") (pin "2") (pinfunction "D-_2") (pintype "bidirectional"))
    )
    (net (code "86") (name "USB_P") (class "Default")
      (node (ref "IC3") (pin "4") (pinfunction "D+_4") (pintype "bidirectional"))
      (node (ref "USB2") (pin "3") (pinfunction "D+_3") (pintype "bidirectional"))
    )
    (net (code "87") (name "VBAT") (class "Default")
      (node (ref "C11") (pin "1") (pinfunction "1_1") (pintype "passive"))
      (node (ref "CLS_4") (pin "5") (pinfunction "5_5") (pintype "passive"))
      (node (ref "IC2") (pin "1") (pinfunction "VBAT_1") (pintype "power_in"))
      (node (ref "JP4") (pin "1") (pinfunction "1_1") (pintype "passive"))
    )
    (net (code "88") (name "VDDA") (class "Default")
      (node (ref "C10") (pin "+") (pinfunction "+_+") (pintype "passive"))
      (node (ref "C9") (pin "1") (pinfunction "1_1") (pintype "passive"))
      (node (ref "FB") (pin "2") (pinfunction "2_2") (pintype "passive"))
      (node (ref "IC2") (pin "13") (pinfunction "VDDA_13") (pintype "power_in"))
    )
    (net (code "89") (name "VDDA_PIN") (class "Default")
      (node (ref "DIGITAL_PIN_8-13") (pin "8") (pinfunction "8_8") (pintype "passive"))
      (node (ref "FB") (pin "1") (pinfunction "1_1") (pintype "passive"))
      (node (ref "JP3") (pin "2") (pinfunction "2_2") (pintype "passive"))
    )
    (net (code "90") (name "VIN") (class "Default")
      (node (ref "F1") (pin "2") (pinfunction "2_2") (pintype "passive"))
      (node (ref "J1") (pin "PWR") (pinfunction "PWR_PWR") (pintype "bidirectional"))
      (node (ref "POWER") (pin "8") (pinfunction "8_8") (pintype "passive"))
    )
    (net (code "91") (name "unconnected-(IC3-CTS-Pad23)") (class "Default")
      (node (ref "IC3") (pin "23") (pinfunction "CTS_23") (pintype "input"))
    )
    (net (code "92") (name "unconnected-(IC3-DCD-Pad1)") (class "Default")
      (node (ref "IC3") (pin "1") (pinfunction "DCD_1") (pintype "input"))
    )
    (net (code "93") (name "unconnected-(IC3-DSR-Pad27)") (class "Default")
      (node (ref "IC3") (pin "27") (pinfunction "DSR_27") (pintype "input"))
    )
    (net (code "94") (name "unconnected-(IC3-DTR-Pad28)") (class "Default")
      (node (ref "IC3") (pin "28") (pinfunction "DTR_28") (pintype "output"))
    )
    (net (code "95") (name "unconnected-(IC3-RI-Pad2)") (class "Default")
      (node (ref "IC3") (pin "2") (pinfunction "RI_2") (pintype "input"))
    )
    (net (code "96") (name "unconnected-(IC3-RTS-Pad24)") (class "Default")
      (node (ref "IC3") (pin "24") (pinfunction "RTS_24") (pintype "output"))
    )
    (net (code "97") (name "unconnected-(IC3-SUSPEND-Pad12)") (class "Default")
      (node (ref "IC3") (pin "12") (pinfunction "SUSPEND_12") (pintype "output"))
    )
    (net (code "98") (name "unconnected-(J1-GNDBREAK-PadGNB)") (class "Default")
      (node (ref "J1") (pin "GNB") (pinfunction "GNDBREAK_GNB") (pintype "bidirectional"))
    )
    (net (code "99") (name "unconnected-(USB1-ID-Pad4)") (class "Default")
      (node (ref "USB1") (pin "4") (pinfunction "ID_4") (pintype "bidirectional"))
    )
    (net (code "100") (name "unconnected-(USB2-ID-Pad4)") (class "Default")
      (node (ref "USB2") (pin "4") (pinfunction "ID_4") (pintype "bidirectional"))
    )
  )
)
